# Plantenbak-v3.net
KiCad netlist of a schematic drawn in EAGLE
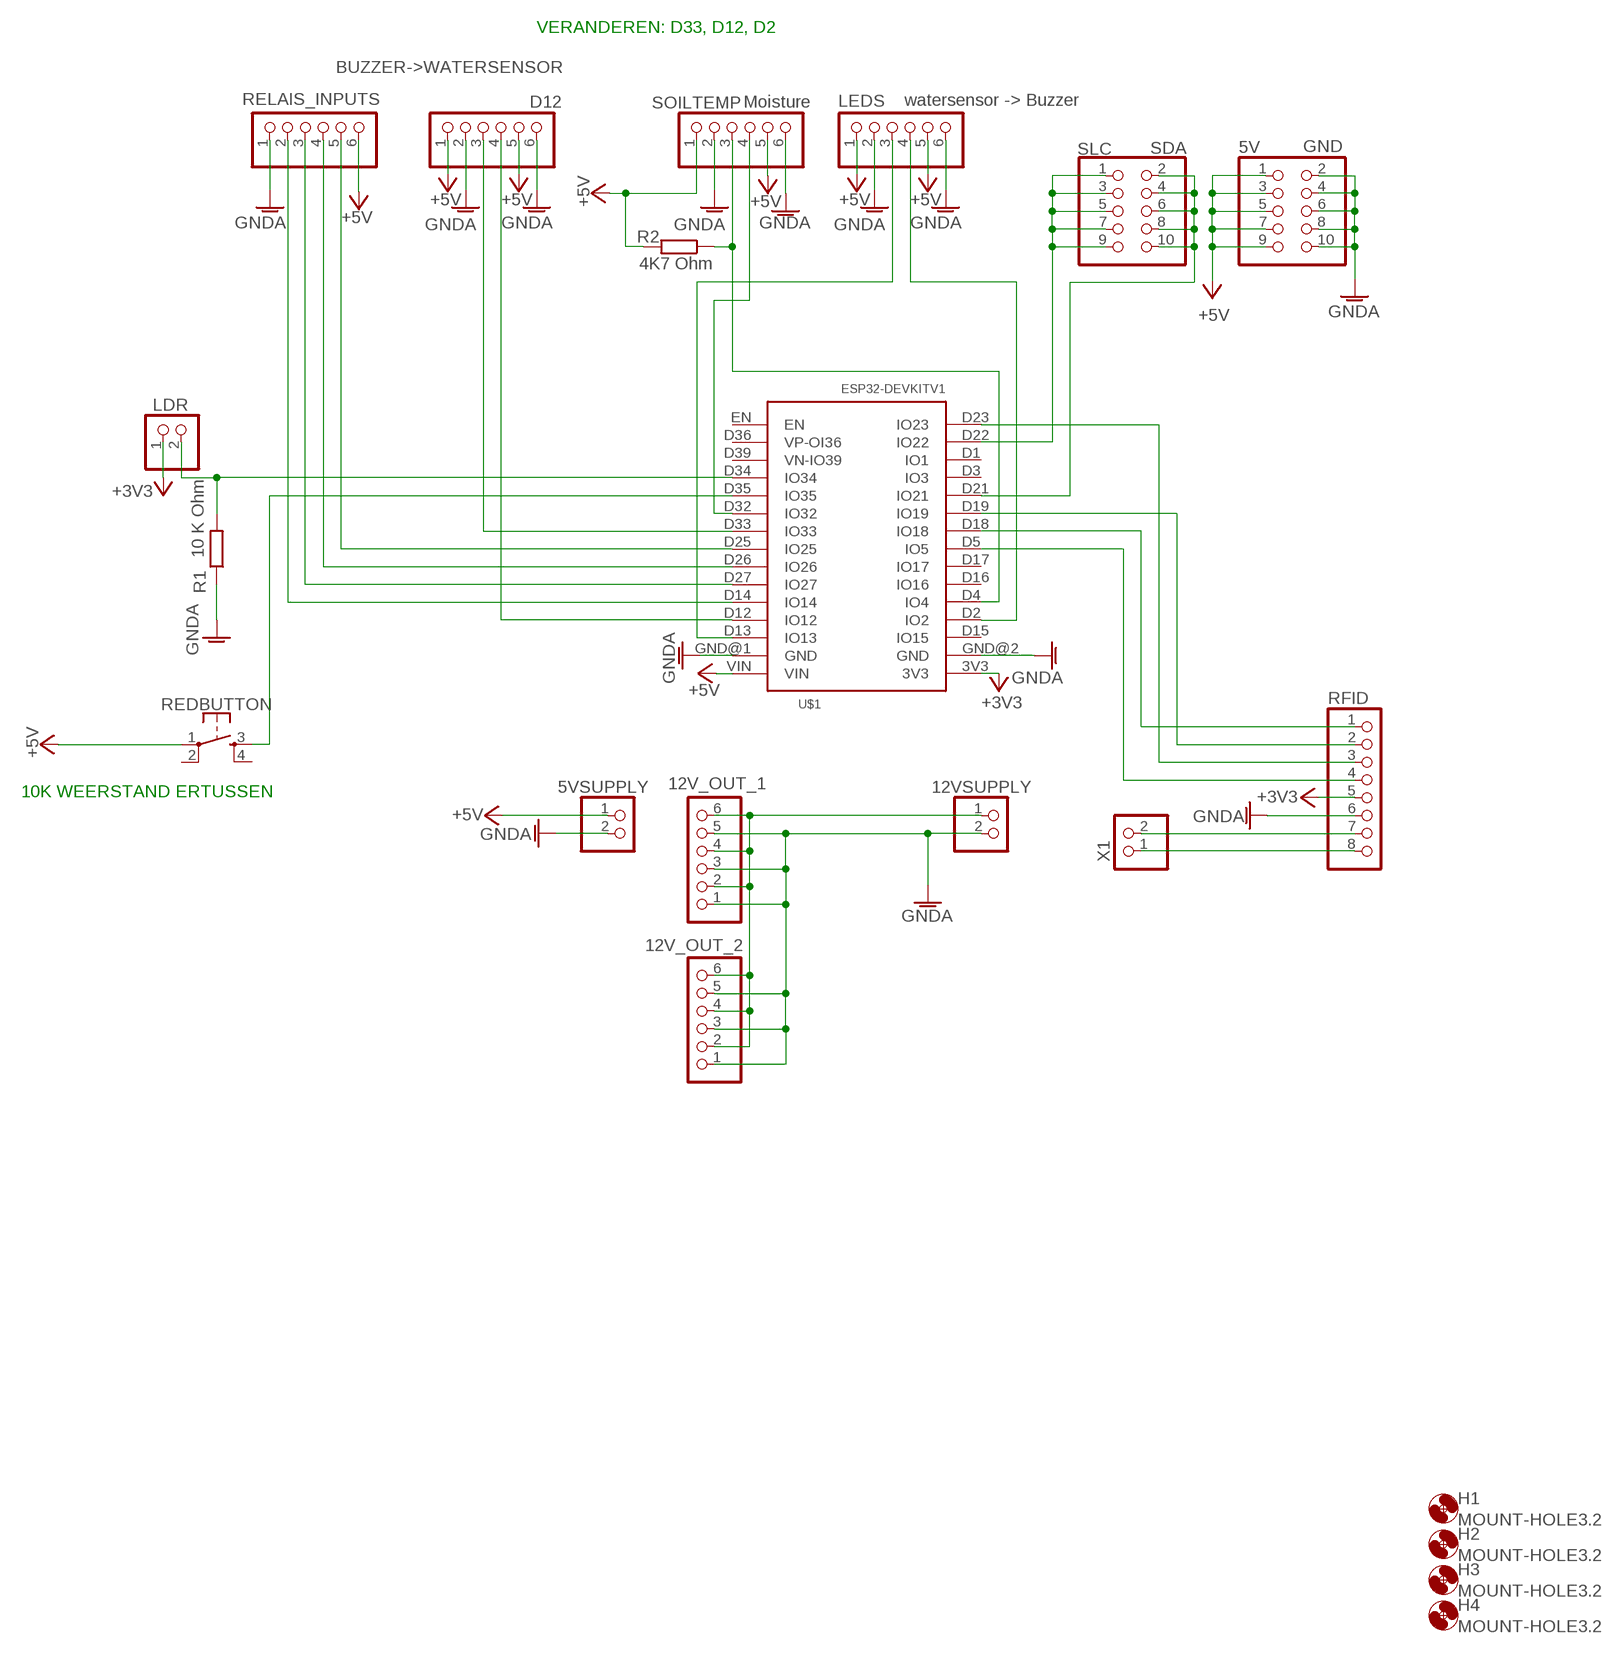
[diagram p0: schematic, sheet 1]

(export (version "E")
  (design (tool "Eeschema 10.0.6"))
  (components
    (comp (ref "5V")
      (value "GND")
      (footprint "eagle-import:2X05")
      (libsource (lib "eagle-import") (part "PINHD-2X5"))
    )
    (comp (ref "5VSUPPLY")
      (value "PINHD-1X2")
      (footprint "eagle-import:1X02")
      (libsource (lib "eagle-import") (part "PINHD-1X2"))
    )
    (comp (ref "12VSUPPLY")
      (value "PINHD-1X2")
      (footprint "eagle-import:1X02")
      (libsource (lib "eagle-import") (part "PINHD-1X2"))
    )
    (comp (ref "12V_OUT_1")
      (value "PINHD-1X6")
      (footprint "eagle-import:1X06")
      (libsource (lib "eagle-import") (part "PINHD-1X6"))
    )
    (comp (ref "12V_OUT_2")
      (value "PINHD-1X6")
      (footprint "eagle-import:1X06")
      (libsource (lib "eagle-import") (part "PINHD-1X6"))
    )
    (comp (ref "BUZZER->WATERSENSOR")
      (value "D12")
      (footprint "eagle-import:1X06")
      (libsource (lib "eagle-import") (part "PINHD-1X6"))
    )
    (comp (ref "H1")
      (value "MOUNT-HOLE3.2")
      (footprint "eagle-import:3,2")
      (libsource (lib "eagle-import") (part "MOUNT-HOLE3.2"))
    )
    (comp (ref "H2")
      (value "MOUNT-HOLE3.2")
      (footprint "eagle-import:3,2")
      (libsource (lib "eagle-import") (part "MOUNT-HOLE3.2"))
    )
    (comp (ref "H3")
      (value "MOUNT-HOLE3.2")
      (footprint "eagle-import:3,2")
      (libsource (lib "eagle-import") (part "MOUNT-HOLE3.2"))
    )
    (comp (ref "H4")
      (value "MOUNT-HOLE3.2")
      (footprint "eagle-import:3,2")
      (libsource (lib "eagle-import") (part "MOUNT-HOLE3.2"))
    )
    (comp (ref "LDR")
      (value "PINHD-1X2")
      (footprint "eagle-import:1X02")
      (libsource (lib "eagle-import") (part "PINHD-1X2"))
    )
    (comp (ref "LEDS")
      (value "watersensor -> Buzzer")
      (footprint "eagle-import:1X06")
      (libsource (lib "eagle-import") (part "PINHD-1X6"))
    )
    (comp (ref "R1")
      (value "10 K Ohm")
      (footprint "eagle-import:0204_7")
      (libsource (lib "eagle-import") (part "R-EU_0204/7"))
    )
    (comp (ref "R2")
      (value "4K7 Ohm")
      (footprint "eagle-import:0204_7")
      (libsource (lib "eagle-import") (part "R-EU_0204/7"))
    )
    (comp (ref "REDBUTTON")
      (value "MOMENTARY-SWITCH-SPST-2-SMD-5.2MM")
      (footprint "eagle-import:TACTILE_SWITCH_SMD_5.2MM")
      (libsource (lib "eagle-import") (part "MOMENTARY-SWITCH-SPST-2-SMD-5.2MM"))
    )
    (comp (ref "RELAIS_INPUTS")
      (value "PINHD-1X6")
      (footprint "eagle-import:1X06")
      (libsource (lib "eagle-import") (part "PINHD-1X6"))
    )
    (comp (ref "RFID")
      (value "PINHD-1X8")
      (footprint "eagle-import:1X08")
      (libsource (lib "eagle-import") (part "PINHD-1X8"))
    )
    (comp (ref "SLC")
      (value "SDA")
      (footprint "eagle-import:2X05")
      (libsource (lib "eagle-import") (part "PINHD-2X5"))
    )
    (comp (ref "SOILTEMP")
      (value "Moisture")
      (footprint "eagle-import:1X06")
      (libsource (lib "eagle-import") (part "PINHD-1X6"))
    )
    (comp (ref "U$1")
      (value "ESP32DEVKITV1")
      (footprint "eagle-import:ESP32-DEVKITV1")
      (libsource (lib "eagle-import") (part "ESP32DEVKITV1"))
    )
    (comp (ref "X1")
      (value "PINHD-1X2")
      (footprint "eagle-import:1X02")
      (libsource (lib "eagle-import") (part "PINHD-1X2"))
    )
  )
  (nets
    (net (code "1") (name "+3V3") (class "Default")
      (node (ref "LDR") (pin "1") (pinfunction "1_1") (pintype "passive"))
      (node (ref "RFID") (pin "5") (pinfunction "5_5") (pintype "passive"))
      (node (ref "U$1") (pin "3V3") (pinfunction "3V3_3V3") (pintype "bidirectional"))
    )
    (net (code "2") (name "+5V") (class "Default")
      (node (ref "5V") (pin "1") (pinfunction "1_1") (pintype "passive"))
      (node (ref "5V") (pin "3") (pinfunction "3_3") (pintype "passive"))
      (node (ref "5V") (pin "5") (pinfunction "5_5") (pintype "passive"))
      (node (ref "5V") (pin "7") (pinfunction "7_7") (pintype "passive"))
      (node (ref "5V") (pin "9") (pinfunction "9_9") (pintype "passive"))
      (node (ref "5VSUPPLY") (pin "1") (pinfunction "1_1") (pintype "passive"))
      (node (ref "BUZZER->WATERSENSOR") (pin "1") (pinfunction "1_1") (pintype "passive"))
      (node (ref "BUZZER->WATERSENSOR") (pin "5") (pinfunction "5_5") (pintype "passive"))
      (node (ref "LEDS") (pin "1") (pinfunction "1_1") (pintype "passive"))
      (node (ref "LEDS") (pin "5") (pinfunction "5_5") (pintype "passive"))
      (node (ref "R2") (pin "2") (pinfunction "2_2") (pintype "passive"))
      (node (ref "REDBUTTON") (pin "1") (pinfunction "1_1") (pintype "passive"))
      (node (ref "RELAIS_INPUTS") (pin "6") (pinfunction "6_6") (pintype "passive"))
      (node (ref "SOILTEMP") (pin "1") (pinfunction "1_1") (pintype "passive"))
      (node (ref "SOILTEMP") (pin "5") (pinfunction "5_5") (pintype "passive"))
      (node (ref "U$1") (pin "VIN") (pinfunction "VIN_VIN") (pintype "bidirectional"))
    )
    (net (code "3") (name "GNDA") (class "Default")
      (node (ref "12VSUPPLY") (pin "2") (pinfunction "2_2") (pintype "passive"))
      (node (ref "12V_OUT_1") (pin "1") (pinfunction "1_1") (pintype "passive"))
      (node (ref "12V_OUT_1") (pin "3") (pinfunction "3_3") (pintype "passive"))
      (node (ref "12V_OUT_1") (pin "5") (pinfunction "5_5") (pintype "passive"))
      (node (ref "12V_OUT_2") (pin "1") (pinfunction "1_1") (pintype "passive"))
      (node (ref "12V_OUT_2") (pin "3") (pinfunction "3_3") (pintype "passive"))
      (node (ref "12V_OUT_2") (pin "5") (pinfunction "5_5") (pintype "passive"))
      (node (ref "5V") (pin "10") (pinfunction "10_10") (pintype "passive"))
      (node (ref "5V") (pin "2") (pinfunction "2_2") (pintype "passive"))
      (node (ref "5V") (pin "4") (pinfunction "4_4") (pintype "passive"))
      (node (ref "5V") (pin "6") (pinfunction "6_6") (pintype "passive"))
      (node (ref "5V") (pin "8") (pinfunction "8_8") (pintype "passive"))
      (node (ref "5VSUPPLY") (pin "2") (pinfunction "2_2") (pintype "passive"))
      (node (ref "BUZZER->WATERSENSOR") (pin "2") (pinfunction "2_2") (pintype "passive"))
      (node (ref "BUZZER->WATERSENSOR") (pin "6") (pinfunction "6_6") (pintype "passive"))
      (node (ref "LEDS") (pin "2") (pinfunction "2_2") (pintype "passive"))
      (node (ref "LEDS") (pin "6") (pinfunction "6_6") (pintype "passive"))
      (node (ref "R1") (pin "1") (pinfunction "1_1") (pintype "passive"))
      (node (ref "RELAIS_INPUTS") (pin "1") (pinfunction "1_1") (pintype "passive"))
      (node (ref "RFID") (pin "6") (pinfunction "6_6") (pintype "passive"))
      (node (ref "SOILTEMP") (pin "2") (pinfunction "2_2") (pintype "passive"))
      (node (ref "SOILTEMP") (pin "6") (pinfunction "6_6") (pintype "passive"))
      (node (ref "U$1") (pin "GND@1") (pinfunction "GND_GND@1") (pintype "bidirectional"))
      (node (ref "U$1") (pin "GND@2") (pinfunction "GND_GND@2") (pintype "bidirectional"))
    )
    (net (code "4") (name "Net-(12VSUPPLY-Pad1)") (class "Default")
      (node (ref "12VSUPPLY") (pin "1") (pinfunction "1_1") (pintype "passive"))
      (node (ref "12V_OUT_1") (pin "2") (pinfunction "2_2") (pintype "passive"))
      (node (ref "12V_OUT_1") (pin "4") (pinfunction "4_4") (pintype "passive"))
      (node (ref "12V_OUT_1") (pin "6") (pinfunction "6_6") (pintype "passive"))
      (node (ref "12V_OUT_2") (pin "2") (pinfunction "2_2") (pintype "passive"))
      (node (ref "12V_OUT_2") (pin "4") (pinfunction "4_4") (pintype "passive"))
      (node (ref "12V_OUT_2") (pin "6") (pinfunction "6_6") (pintype "passive"))
    )
    (net (code "5") (name "Net-(RFID-Pad7)") (class "Default")
      (node (ref "RFID") (pin "7") (pinfunction "7_7") (pintype "passive"))
      (node (ref "X1") (pin "2") (pinfunction "2_2") (pintype "passive"))
    )
    (net (code "6") (name "Net-(RFID-Pad8)") (class "Default")
      (node (ref "RFID") (pin "8") (pinfunction "8_8") (pintype "passive"))
      (node (ref "X1") (pin "1") (pinfunction "1_1") (pintype "passive"))
    )
    (net (code "7") (name "Net-(U$1-IO2)") (class "Default")
      (node (ref "LEDS") (pin "4") (pinfunction "4_4") (pintype "passive"))
      (node (ref "U$1") (pin "D2") (pinfunction "IO2_D2") (pintype "bidirectional"))
    )
    (net (code "8") (name "Net-(U$1-IO4)") (class "Default")
      (node (ref "R2") (pin "1") (pinfunction "1_1") (pintype "passive"))
      (node (ref "SOILTEMP") (pin "3") (pinfunction "3_3") (pintype "passive"))
      (node (ref "U$1") (pin "D4") (pinfunction "IO4_D4") (pintype "bidirectional"))
    )
    (net (code "9") (name "Net-(U$1-IO5)") (class "Default")
      (node (ref "RFID") (pin "4") (pinfunction "4_4") (pintype "passive"))
      (node (ref "U$1") (pin "D5") (pinfunction "IO5_D5") (pintype "bidirectional"))
    )
    (net (code "10") (name "Net-(U$1-IO12)") (class "Default")
      (node (ref "BUZZER->WATERSENSOR") (pin "4") (pinfunction "4_4") (pintype "passive"))
      (node (ref "U$1") (pin "D12") (pinfunction "IO12_D12") (pintype "bidirectional"))
    )
    (net (code "11") (name "Net-(U$1-IO13)") (class "Default")
      (node (ref "LEDS") (pin "3") (pinfunction "3_3") (pintype "passive"))
      (node (ref "U$1") (pin "D13") (pinfunction "IO13_D13") (pintype "bidirectional"))
    )
    (net (code "12") (name "Net-(U$1-IO14)") (class "Default")
      (node (ref "RELAIS_INPUTS") (pin "2") (pinfunction "2_2") (pintype "passive"))
      (node (ref "U$1") (pin "D14") (pinfunction "IO14_D14") (pintype "bidirectional"))
    )
    (net (code "13") (name "Net-(U$1-IO18)") (class "Default")
      (node (ref "RFID") (pin "1") (pinfunction "1_1") (pintype "passive"))
      (node (ref "U$1") (pin "D18") (pinfunction "IO18_D18") (pintype "bidirectional"))
    )
    (net (code "14") (name "Net-(U$1-IO19)") (class "Default")
      (node (ref "RFID") (pin "2") (pinfunction "2_2") (pintype "passive"))
      (node (ref "U$1") (pin "D19") (pinfunction "IO19_D19") (pintype "bidirectional"))
    )
    (net (code "15") (name "Net-(U$1-IO21)") (class "Default")
      (node (ref "SLC") (pin "10") (pinfunction "10_10") (pintype "passive"))
      (node (ref "SLC") (pin "2") (pinfunction "2_2") (pintype "passive"))
      (node (ref "SLC") (pin "4") (pinfunction "4_4") (pintype "passive"))
      (node (ref "SLC") (pin "6") (pinfunction "6_6") (pintype "passive"))
      (node (ref "SLC") (pin "8") (pinfunction "8_8") (pintype "passive"))
      (node (ref "U$1") (pin "D21") (pinfunction "IO21_D21") (pintype "bidirectional"))
    )
    (net (code "16") (name "Net-(U$1-IO22)") (class "Default")
      (node (ref "SLC") (pin "1") (pinfunction "1_1") (pintype "passive"))
      (node (ref "SLC") (pin "3") (pinfunction "3_3") (pintype "passive"))
      (node (ref "SLC") (pin "5") (pinfunction "5_5") (pintype "passive"))
      (node (ref "SLC") (pin "7") (pinfunction "7_7") (pintype "passive"))
      (node (ref "SLC") (pin "9") (pinfunction "9_9") (pintype "passive"))
      (node (ref "U$1") (pin "D22") (pinfunction "IO22_D22") (pintype "bidirectional"))
    )
    (net (code "17") (name "Net-(U$1-IO23)") (class "Default")
      (node (ref "RFID") (pin "3") (pinfunction "3_3") (pintype "passive"))
      (node (ref "U$1") (pin "D23") (pinfunction "IO23_D23") (pintype "bidirectional"))
    )
    (net (code "18") (name "Net-(U$1-IO25)") (class "Default")
      (node (ref "RELAIS_INPUTS") (pin "5") (pinfunction "5_5") (pintype "passive"))
      (node (ref "U$1") (pin "D25") (pinfunction "IO25_D25") (pintype "bidirectional"))
    )
    (net (code "19") (name "Net-(U$1-IO26)") (class "Default")
      (node (ref "RELAIS_INPUTS") (pin "4") (pinfunction "4_4") (pintype "passive"))
      (node (ref "U$1") (pin "D26") (pinfunction "IO26_D26") (pintype "bidirectional"))
    )
    (net (code "20") (name "Net-(U$1-IO27)") (class "Default")
      (node (ref "RELAIS_INPUTS") (pin "3") (pinfunction "3_3") (pintype "passive"))
      (node (ref "U$1") (pin "D27") (pinfunction "IO27_D27") (pintype "bidirectional"))
    )
    (net (code "21") (name "Net-(U$1-IO32)") (class "Default")
      (node (ref "SOILTEMP") (pin "4") (pinfunction "4_4") (pintype "passive"))
      (node (ref "U$1") (pin "D32") (pinfunction "IO32_D32") (pintype "bidirectional"))
    )
    (net (code "22") (name "Net-(U$1-IO33)") (class "Default")
      (node (ref "BUZZER->WATERSENSOR") (pin "3") (pinfunction "3_3") (pintype "passive"))
      (node (ref "U$1") (pin "D33") (pinfunction "IO33_D33") (pintype "bidirectional"))
    )
    (net (code "23") (name "Net-(U$1-IO34)") (class "Default")
      (node (ref "LDR") (pin "2") (pinfunction "2_2") (pintype "passive"))
      (node (ref "R1") (pin "2") (pinfunction "2_2") (pintype "passive"))
      (node (ref "U$1") (pin "D34") (pinfunction "IO34_D34") (pintype "bidirectional"))
    )
    (net (code "24") (name "Net-(U$1-IO35)") (class "Default")
      (node (ref "REDBUTTON") (pin "3") (pinfunction "3_3") (pintype "passive"))
      (node (ref "U$1") (pin "D35") (pinfunction "IO35_D35") (pintype "bidirectional"))
    )
    (net (code "25") (name "unconnected-(REDBUTTON-Pad2)") (class "Default")
      (node (ref "REDBUTTON") (pin "2") (pinfunction "2_2") (pintype "passive"))
    )
    (net (code "26") (name "unconnected-(REDBUTTON-Pad4)") (class "Default")
      (node (ref "REDBUTTON") (pin "4") (pinfunction "4_4") (pintype "passive"))
    )
    (net (code "27") (name "unconnected-(U$1-IO1-PadD1)") (class "Default")
      (node (ref "U$1") (pin "D1") (pinfunction "IO1_D1") (pintype "bidirectional"))
    )
    (net (code "28") (name "unconnected-(U$1-IO3-PadD3)") (class "Default")
      (node (ref "U$1") (pin "D3") (pinfunction "IO3_D3") (pintype "bidirectional"))
    )
    (net (code "29") (name "unconnected-(U$1-IO15-PadD15)") (class "Default")
      (node (ref "U$1") (pin "D15") (pinfunction "IO15_D15") (pintype "bidirectional"))
    )
    (net (code "30") (name "unconnected-(U$1-IO16-PadD16)") (class "Default")
      (node (ref "U$1") (pin "D16") (pinfunction "IO16_D16") (pintype "bidirectional"))
    )
    (net (code "31") (name "unconnected-(U$1-IO17-PadD17)") (class "Default")
      (node (ref "U$1") (pin "D17") (pinfunction "IO17_D17") (pintype "bidirectional"))
    )
    (net (code "32") (name "unconnected-(U$1-PadEN)") (class "Default")
      (node (ref "U$1") (pin "EN") (pinfunction "EN_EN") (pintype "bidirectional"))
    )
    (net (code "33") (name "unconnected-(U$1-VN-IO39-PadD39)") (class "Default")
      (node (ref "U$1") (pin "D39") (pinfunction "VN-IO39_D39") (pintype "bidirectional"))
    )
    (net (code "34") (name "unconnected-(U$1-VP-OI36-PadD36)") (class "Default")
      (node (ref "U$1") (pin "D36") (pinfunction "VP-OI36_D36") (pintype "bidirectional"))
    )
  )
)
